# MOTORDRIVERTEST.net
KiCad netlist of a schematic drawn in EasyEDA Pro
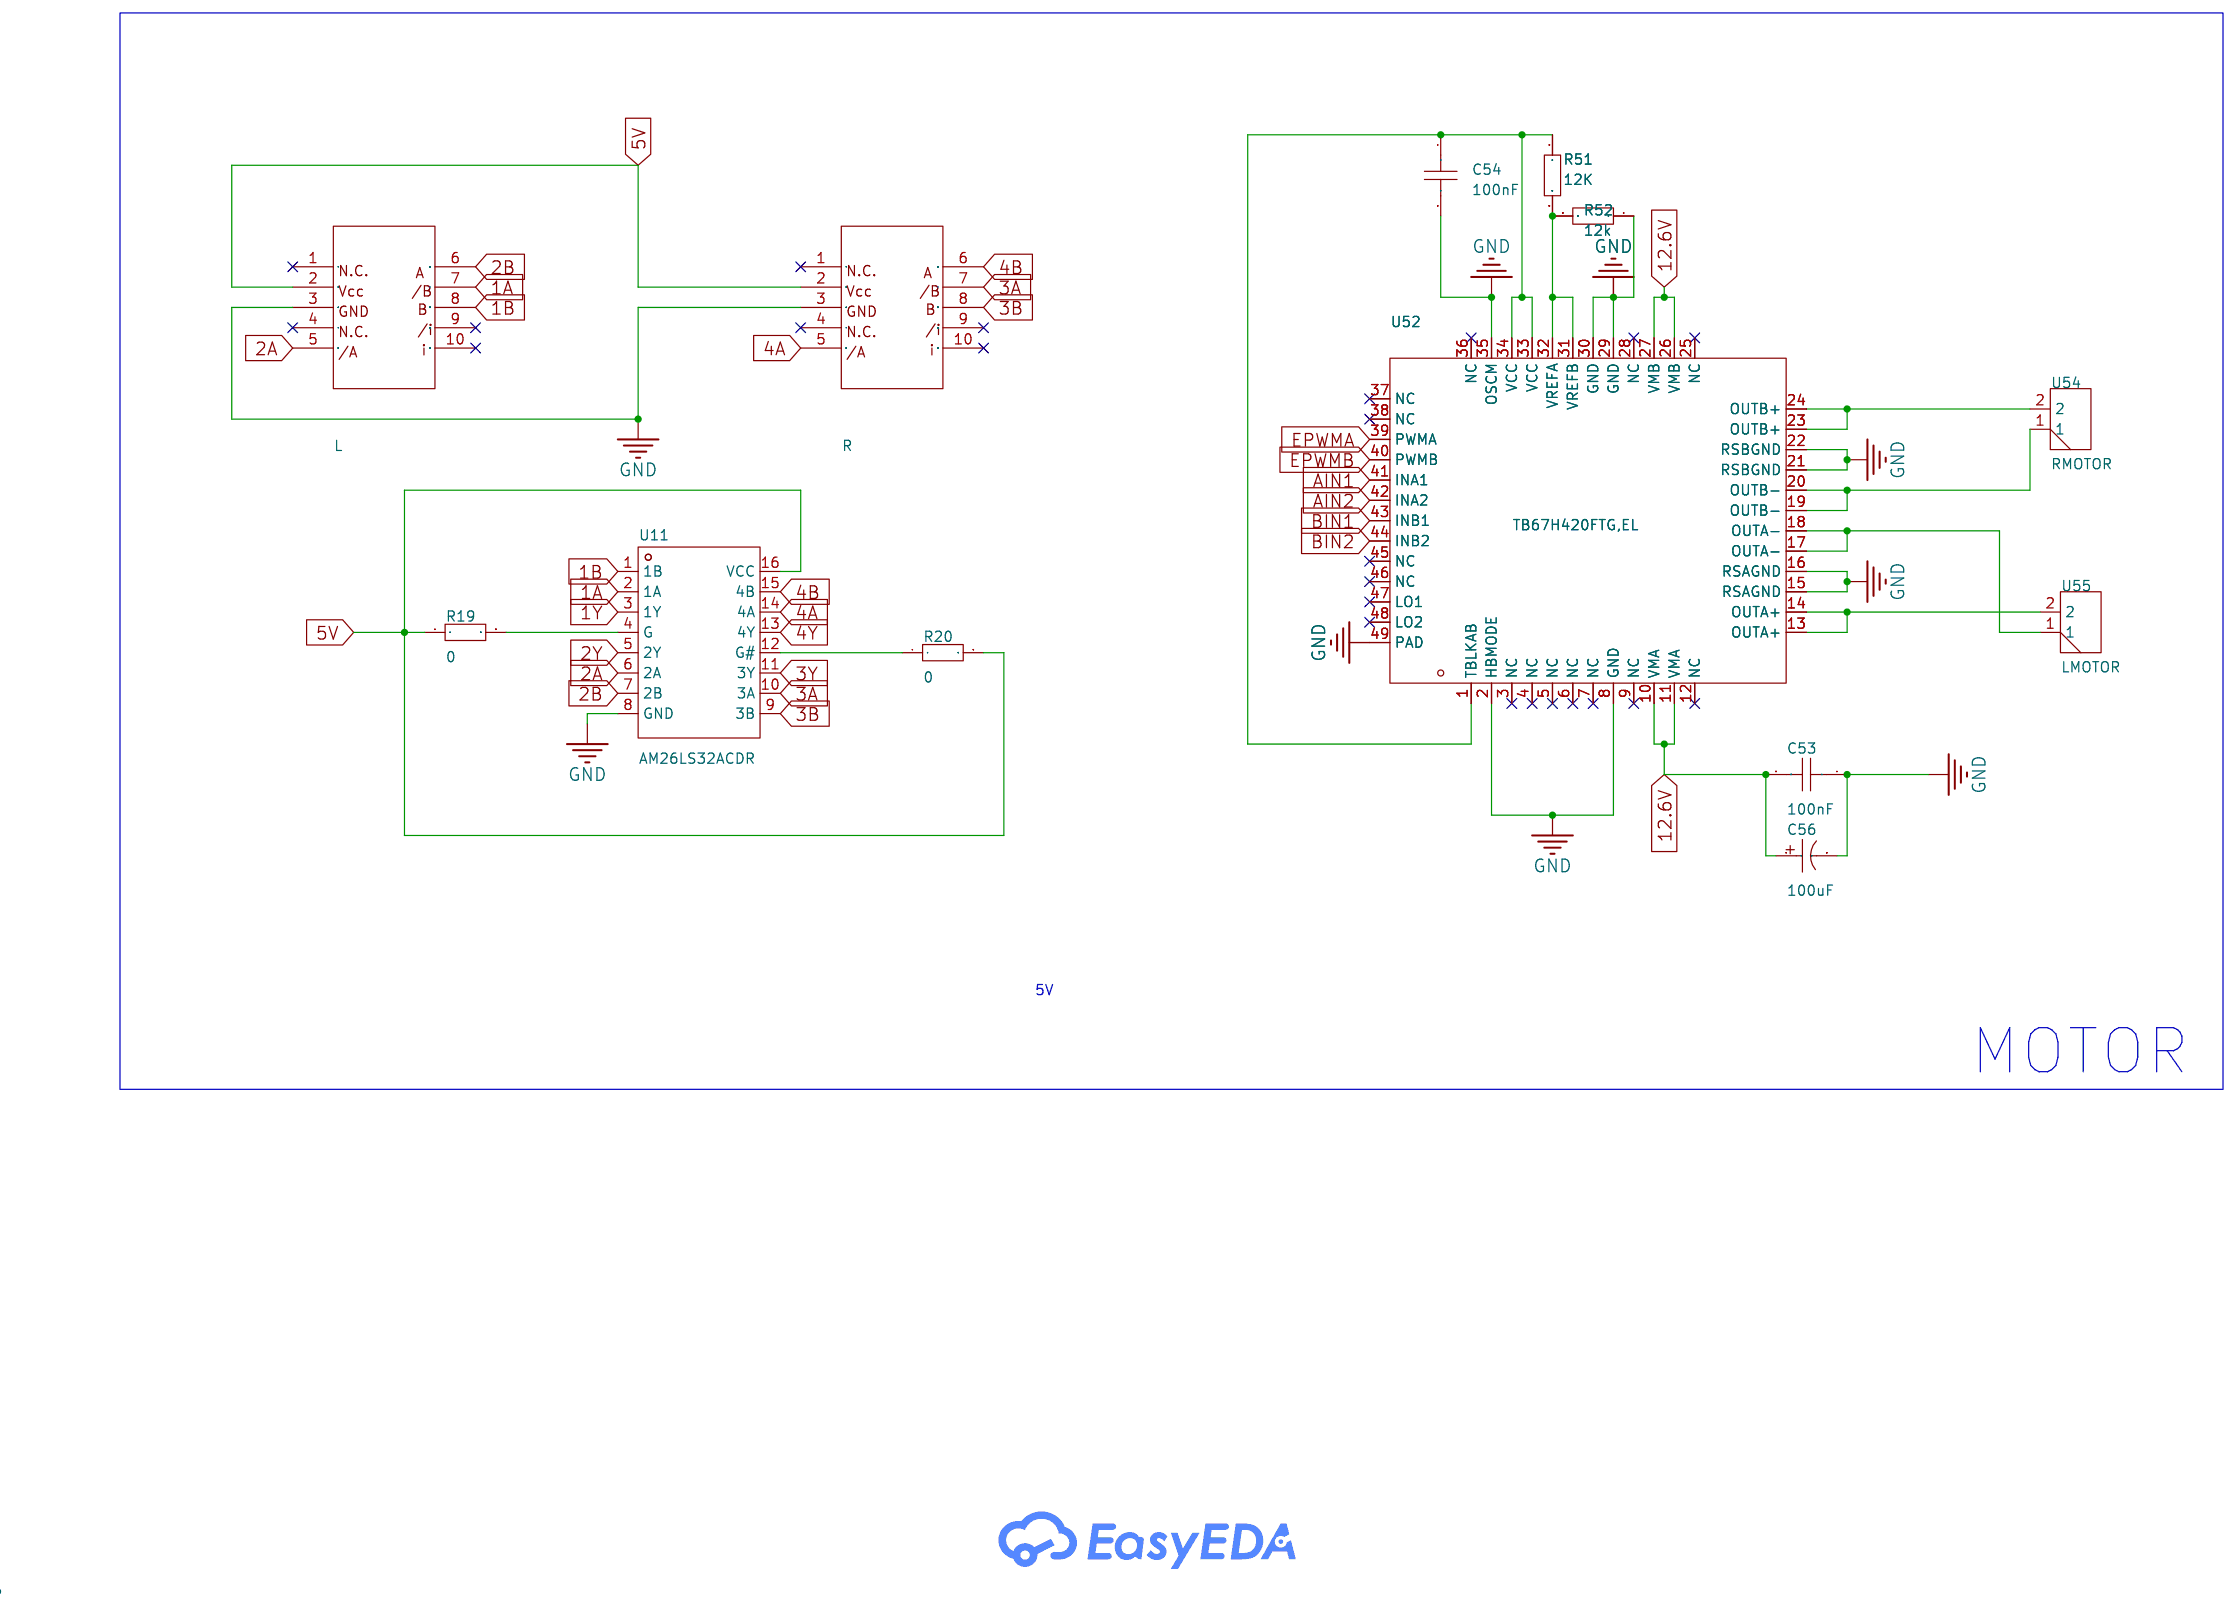
[diagram p0: schematic sheet]

(export (version "E")
  (design (tool "Eeschema 10.0.6"))
  (components
    (comp (ref "C53")
      (value "100nF")
      (footprint "easyedapro:C0603")
      (libsource (lib "easyedapro") (part "CAP"))
    )
    (comp (ref "C54")
      (value "100nF")
      (footprint "easyedapro:C0603")
      (libsource (lib "easyedapro") (part "CAP"))
    )
    (comp (ref "C56")
      (value "100uF")
      (footprint "easyedapro:CAP-SMD_BD6.3-L6.6-W6.6-FD")
      (fields (field (name "Manufacturer Part") "RT1C101M0605") (field (name "Manufacturer") "ROQANG(容强)"))
      (libsource (lib "easyedapro") (part "RT1C101M0605"))
    )
    (comp (ref "R19") (value "0") (footprint "easyedapro:R0603") (libsource (lib "easyedapro") (part "Res")))
    (comp (ref "R20") (value "0") (footprint "easyedapro:R0603") (libsource (lib "easyedapro") (part "Res")))
    (comp (ref "R51")
      (value "12K")
      (footprint "easyedapro:R0603")
      (libsource (lib "easyedapro") (part "Res"))
    )
    (comp (ref "R52")
      (value "12k")
      (footprint "easyedapro:R0603")
      (libsource (lib "easyedapro") (part "Res"))
    )
    (comp (ref "U11")
      (value "AM26LS32ACDR")
      (footprint "easyedapro:SOIC-16_L9.9-W3.9-P1.27-LS6.0-BL")
      (fields (field (name "Manufacturer") "TI(德州仪器)"))
      (libsource (lib "easyedapro") (part "AM26LS32ACDR"))
    )
    (comp (ref "U50")
      (value "L")
      (footprint "easyedapro:Encoder")
      (libsource (lib "easyedapro") (part "Encoder"))
    )
    (comp (ref "U51")
      (value "R")
      (footprint "easyedapro:Encoder")
      (libsource (lib "easyedapro") (part "Encoder"))
    )
    (comp (ref "U52")
      (value "TB67H420FTG,EL")
      (footprint "easyedapro:QFN-48_L7.0-W7.0-P0.50-BL-EP5.4")
      (fields (field (name "Manufacturer") "TOSHIBA(东芝)"))
      (libsource (lib "easyedapro") (part "TB67H420FTG,EL"))
    )
    (comp (ref "U54")
      (value "RMOTOR")
      (footprint "easyedapro:5267_2P")
      (libsource (lib "easyedapro") (part "Molex_5267_2P"))
    )
    (comp (ref "U55")
      (value "LMOTOR")
      (footprint "easyedapro:5267_2P")
      (libsource (lib "easyedapro") (part "Molex_5267_2P"))
    )
  )
  (nets
    (net (code "1") (name "1A") (class "Default")
      (node (ref "U11") (pin "2") (pinfunction "1A_2") (pintype "unspecified"))
      (node (ref "U50") (pin "7") (pinfunction "7_7") (pintype "input"))
    )
    (net (code "2") (name "1B") (class "Default")
      (node (ref "U11") (pin "1") (pinfunction "1B_1") (pintype "unspecified"))
      (node (ref "U50") (pin "8") (pinfunction "8_8") (pintype "input"))
    )
    (net (code "3") (name "1Y") (class "Default")
      (node (ref "U11") (pin "3") (pinfunction "1Y_3") (pintype "unspecified"))
    )
    (net (code "4") (name "2A") (class "Default")
      (node (ref "U11") (pin "6") (pinfunction "2A_6") (pintype "unspecified"))
      (node (ref "U50") (pin "5") (pinfunction "5_5") (pintype "input"))
    )
    (net (code "5") (name "2B") (class "Default")
      (node (ref "U11") (pin "7") (pinfunction "2B_7") (pintype "unspecified"))
      (node (ref "U50") (pin "6") (pinfunction "6_6") (pintype "input"))
    )
    (net (code "6") (name "2Y") (class "Default")
      (node (ref "U11") (pin "5") (pinfunction "2Y_5") (pintype "unspecified"))
    )
    (net (code "7") (name "3A") (class "Default")
      (node (ref "U11") (pin "10") (pinfunction "3A_10") (pintype "unspecified"))
      (node (ref "U51") (pin "7") (pinfunction "7_7") (pintype "input"))
    )
    (net (code "8") (name "3B") (class "Default")
      (node (ref "U11") (pin "9") (pinfunction "3B_9") (pintype "unspecified"))
      (node (ref "U51") (pin "8") (pinfunction "8_8") (pintype "input"))
    )
    (net (code "9") (name "3Y") (class "Default")
      (node (ref "U11") (pin "11") (pinfunction "3Y_11") (pintype "unspecified"))
    )
    (net (code "10") (name "4A") (class "Default")
      (node (ref "U11") (pin "14") (pinfunction "4A_14") (pintype "unspecified"))
      (node (ref "U51") (pin "5") (pinfunction "5_5") (pintype "input"))
    )
    (net (code "11") (name "4B") (class "Default")
      (node (ref "U11") (pin "15") (pinfunction "4B_15") (pintype "unspecified"))
      (node (ref "U51") (pin "6") (pinfunction "6_6") (pintype "input"))
    )
    (net (code "12") (name "4Y") (class "Default")
      (node (ref "U11") (pin "13") (pinfunction "4Y_13") (pintype "unspecified"))
    )
    (net (code "13") (name "5V") (class "Default")
      (node (ref "R19") (pin "1") (pinfunction "1_1") (pintype "input"))
      (node (ref "R20") (pin "2") (pinfunction "2_2") (pintype "input"))
      (node (ref "U11") (pin "16") (pinfunction "VCC_16") (pintype "unspecified"))
      (node (ref "U50") (pin "2") (pinfunction "2_2") (pintype "input"))
      (node (ref "U51") (pin "2") (pinfunction "2_2") (pintype "input"))
    )
    (net (code "14") (name "12.6V") (class "Default")
      (node (ref "C53") (pin "2") (pinfunction "2_2") (pintype "input"))
      (node (ref "C56") (pin "1") (pinfunction "1_1") (pintype "input"))
      (node (ref "U52") (pin "10") (pinfunction "VMA_10") (pintype "unspecified"))
      (node (ref "U52") (pin "11") (pinfunction "VMA_11") (pintype "unspecified"))
      (node (ref "U52") (pin "26") (pinfunction "VMB_26") (pintype "unspecified"))
      (node (ref "U52") (pin "27") (pinfunction "VMB_27") (pintype "unspecified"))
    )
    (net (code "15") (name "AIN1") (class "Default")
      (node (ref "U52") (pin "41") (pinfunction "INA1_41") (pintype "unspecified"))
    )
    (net (code "16") (name "AIN2") (class "Default")
      (node (ref "U52") (pin "42") (pinfunction "INA2_42") (pintype "unspecified"))
    )
    (net (code "17") (name "BIN1") (class "Default")
      (node (ref "U52") (pin "43") (pinfunction "INB1_43") (pintype "unspecified"))
    )
    (net (code "18") (name "BIN2") (class "Default")
      (node (ref "U52") (pin "44") (pinfunction "INB2_44") (pintype "unspecified"))
    )
    (net (code "19") (name "EPWMA") (class "Default")
      (node (ref "U52") (pin "39") (pinfunction "PWMA_39") (pintype "unspecified"))
    )
    (net (code "20") (name "EPWMB") (class "Default")
      (node (ref "U52") (pin "40") (pinfunction "PWMB_40") (pintype "unspecified"))
    )
    (net (code "21") (name "GND") (class "Default")
      (node (ref "C53") (pin "1") (pinfunction "1_1") (pintype "input"))
      (node (ref "C54") (pin "2") (pinfunction "2_2") (pintype "input"))
      (node (ref "C56") (pin "2") (pinfunction "2_2") (pintype "input"))
      (node (ref "R52") (pin "1") (pinfunction "1_1") (pintype "input"))
      (node (ref "U11") (pin "8") (pinfunction "GND_8") (pintype "unspecified"))
      (node (ref "U50") (pin "3") (pinfunction "3_3") (pintype "input"))
      (node (ref "U51") (pin "3") (pinfunction "3_3") (pintype "input"))
      (node (ref "U52") (pin "15") (pinfunction "RSAGND_15") (pintype "unspecified"))
      (node (ref "U52") (pin "16") (pinfunction "RSAGND_16") (pintype "unspecified"))
      (node (ref "U52") (pin "2") (pinfunction "HBMODE_2") (pintype "unspecified"))
      (node (ref "U52") (pin "21") (pinfunction "RSBGND_21") (pintype "unspecified"))
      (node (ref "U52") (pin "22") (pinfunction "RSBGND_22") (pintype "unspecified"))
      (node (ref "U52") (pin "29") (pinfunction "GND_29") (pintype "unspecified"))
      (node (ref "U52") (pin "30") (pinfunction "GND_30") (pintype "unspecified"))
      (node (ref "U52") (pin "35") (pinfunction "OSCM_35") (pintype "unspecified"))
      (node (ref "U52") (pin "49") (pinfunction "PAD_49") (pintype "unspecified"))
      (node (ref "U52") (pin "8") (pinfunction "GND_8") (pintype "unspecified"))
    )
    (net (code "22") (name "Net-(U11-G#)") (class "Default")
      (node (ref "R20") (pin "1") (pinfunction "1_1") (pintype "input"))
      (node (ref "U11") (pin "12") (pinfunction "G#_12") (pintype "unspecified"))
    )
    (net (code "23") (name "Net-(U11-G)") (class "Default")
      (node (ref "R19") (pin "2") (pinfunction "2_2") (pintype "input"))
      (node (ref "U11") (pin "4") (pinfunction "G_4") (pintype "unspecified"))
    )
    (net (code "24") (name "Net-(U52-OUTA+-Pad13)") (class "Default")
      (node (ref "U52") (pin "13") (pinfunction "OUTA+_13") (pintype "unspecified"))
      (node (ref "U52") (pin "14") (pinfunction "OUTA+_14") (pintype "unspecified"))
      (node (ref "U55") (pin "2") (pinfunction "2_2") (pintype "unspecified"))
    )
    (net (code "25") (name "Net-(U52-OUTA--Pad17)") (class "Default")
      (node (ref "U52") (pin "17") (pinfunction "OUTA-_17") (pintype "unspecified"))
      (node (ref "U52") (pin "18") (pinfunction "OUTA-_18") (pintype "unspecified"))
      (node (ref "U55") (pin "1") (pinfunction "1_1") (pintype "unspecified"))
    )
    (net (code "26") (name "Net-(U52-OUTB+-Pad23)") (class "Default")
      (node (ref "U52") (pin "23") (pinfunction "OUTB+_23") (pintype "unspecified"))
      (node (ref "U52") (pin "24") (pinfunction "OUTB+_24") (pintype "unspecified"))
      (node (ref "U54") (pin "2") (pinfunction "2_2") (pintype "unspecified"))
    )
    (net (code "27") (name "Net-(U52-OUTB--Pad19)") (class "Default")
      (node (ref "U52") (pin "19") (pinfunction "OUTB-_19") (pintype "unspecified"))
      (node (ref "U52") (pin "20") (pinfunction "OUTB-_20") (pintype "unspecified"))
      (node (ref "U54") (pin "1") (pinfunction "1_1") (pintype "unspecified"))
    )
    (net (code "28") (name "Net-(U52-TBLKAB)") (class "Default")
      (node (ref "C54") (pin "1") (pinfunction "1_1") (pintype "input"))
      (node (ref "R51") (pin "1") (pinfunction "1_1") (pintype "input"))
      (node (ref "U52") (pin "1") (pinfunction "TBLKAB_1") (pintype "unspecified"))
      (node (ref "U52") (pin "33") (pinfunction "VCC_33") (pintype "unspecified"))
      (node (ref "U52") (pin "34") (pinfunction "VCC_34") (pintype "unspecified"))
    )
    (net (code "29") (name "Net-(U52-VREFA)") (class "Default")
      (node (ref "R51") (pin "2") (pinfunction "2_2") (pintype "input"))
      (node (ref "R52") (pin "2") (pinfunction "2_2") (pintype "input"))
      (node (ref "U52") (pin "31") (pinfunction "VREFB_31") (pintype "unspecified"))
      (node (ref "U52") (pin "32") (pinfunction "VREFA_32") (pintype "unspecified"))
    )
    (net (code "30") (name "unconnected-(U50-Pad1)") (class "Default")
      (node (ref "U50") (pin "1") (pinfunction "1_1") (pintype "input+no_connect"))
    )
    (net (code "31") (name "unconnected-(U50-Pad4)") (class "Default")
      (node (ref "U50") (pin "4") (pinfunction "4_4") (pintype "input+no_connect"))
    )
    (net (code "32") (name "unconnected-(U50-Pad9)") (class "Default")
      (node (ref "U50") (pin "9") (pinfunction "9_9") (pintype "input+no_connect"))
    )
    (net (code "33") (name "unconnected-(U50-Pad10)") (class "Default")
      (node (ref "U50") (pin "10") (pinfunction "10_10") (pintype "input+no_connect"))
    )
    (net (code "34") (name "unconnected-(U51-Pad1)") (class "Default")
      (node (ref "U51") (pin "1") (pinfunction "1_1") (pintype "input+no_connect"))
    )
    (net (code "35") (name "unconnected-(U51-Pad4)") (class "Default")
      (node (ref "U51") (pin "4") (pinfunction "4_4") (pintype "input+no_connect"))
    )
    (net (code "36") (name "unconnected-(U51-Pad9)") (class "Default")
      (node (ref "U51") (pin "9") (pinfunction "9_9") (pintype "input+no_connect"))
    )
    (net (code "37") (name "unconnected-(U51-Pad10)") (class "Default")
      (node (ref "U51") (pin "10") (pinfunction "10_10") (pintype "input+no_connect"))
    )
    (net (code "38") (name "unconnected-(U52-LO1-Pad47)") (class "Default")
      (node (ref "U52") (pin "47") (pinfunction "LO1_47") (pintype "unspecified+no_connect"))
    )
    (net (code "39") (name "unconnected-(U52-LO2-Pad48)") (class "Default")
      (node (ref "U52") (pin "48") (pinfunction "LO2_48") (pintype "unspecified+no_connect"))
    )
    (net (code "40") (name "unconnected-(U52-NC-Pad3)") (class "Default")
      (node (ref "U52") (pin "3") (pinfunction "NC_3") (pintype "unspecified+no_connect"))
    )
    (net (code "41") (name "unconnected-(U52-NC-Pad4)") (class "Default")
      (node (ref "U52") (pin "4") (pinfunction "NC_4") (pintype "unspecified+no_connect"))
    )
    (net (code "42") (name "unconnected-(U52-NC-Pad5)") (class "Default")
      (node (ref "U52") (pin "5") (pinfunction "NC_5") (pintype "unspecified+no_connect"))
    )
    (net (code "43") (name "unconnected-(U52-NC-Pad6)") (class "Default")
      (node (ref "U52") (pin "6") (pinfunction "NC_6") (pintype "unspecified+no_connect"))
    )
    (net (code "44") (name "unconnected-(U52-NC-Pad7)") (class "Default")
      (node (ref "U52") (pin "7") (pinfunction "NC_7") (pintype "unspecified+no_connect"))
    )
    (net (code "45") (name "unconnected-(U52-NC-Pad9)") (class "Default")
      (node (ref "U52") (pin "9") (pinfunction "NC_9") (pintype "unspecified+no_connect"))
    )
    (net (code "46") (name "unconnected-(U52-NC-Pad12)") (class "Default")
      (node (ref "U52") (pin "12") (pinfunction "NC_12") (pintype "unspecified+no_connect"))
    )
    (net (code "47") (name "unconnected-(U52-NC-Pad25)") (class "Default")
      (node (ref "U52") (pin "25") (pinfunction "NC_25") (pintype "unspecified+no_connect"))
    )
    (net (code "48") (name "unconnected-(U52-NC-Pad28)") (class "Default")
      (node (ref "U52") (pin "28") (pinfunction "NC_28") (pintype "unspecified+no_connect"))
    )
    (net (code "49") (name "unconnected-(U52-NC-Pad36)") (class "Default")
      (node (ref "U52") (pin "36") (pinfunction "NC_36") (pintype "unspecified+no_connect"))
    )
    (net (code "50") (name "unconnected-(U52-NC-Pad37)") (class "Default")
      (node (ref "U52") (pin "37") (pinfunction "NC_37") (pintype "unspecified+no_connect"))
    )
    (net (code "51") (name "unconnected-(U52-NC-Pad38)") (class "Default")
      (node (ref "U52") (pin "38") (pinfunction "NC_38") (pintype "unspecified+no_connect"))
    )
    (net (code "52") (name "unconnected-(U52-NC-Pad45)") (class "Default")
      (node (ref "U52") (pin "45") (pinfunction "NC_45") (pintype "unspecified+no_connect"))
    )
    (net (code "53") (name "unconnected-(U52-NC-Pad46)") (class "Default")
      (node (ref "U52") (pin "46") (pinfunction "NC_46") (pintype "unspecified+no_connect"))
    )
  )
)
